# Mach_dieu_khien_tu_xa.net
KiCad netlist of a schematic drawn in Altium Designer
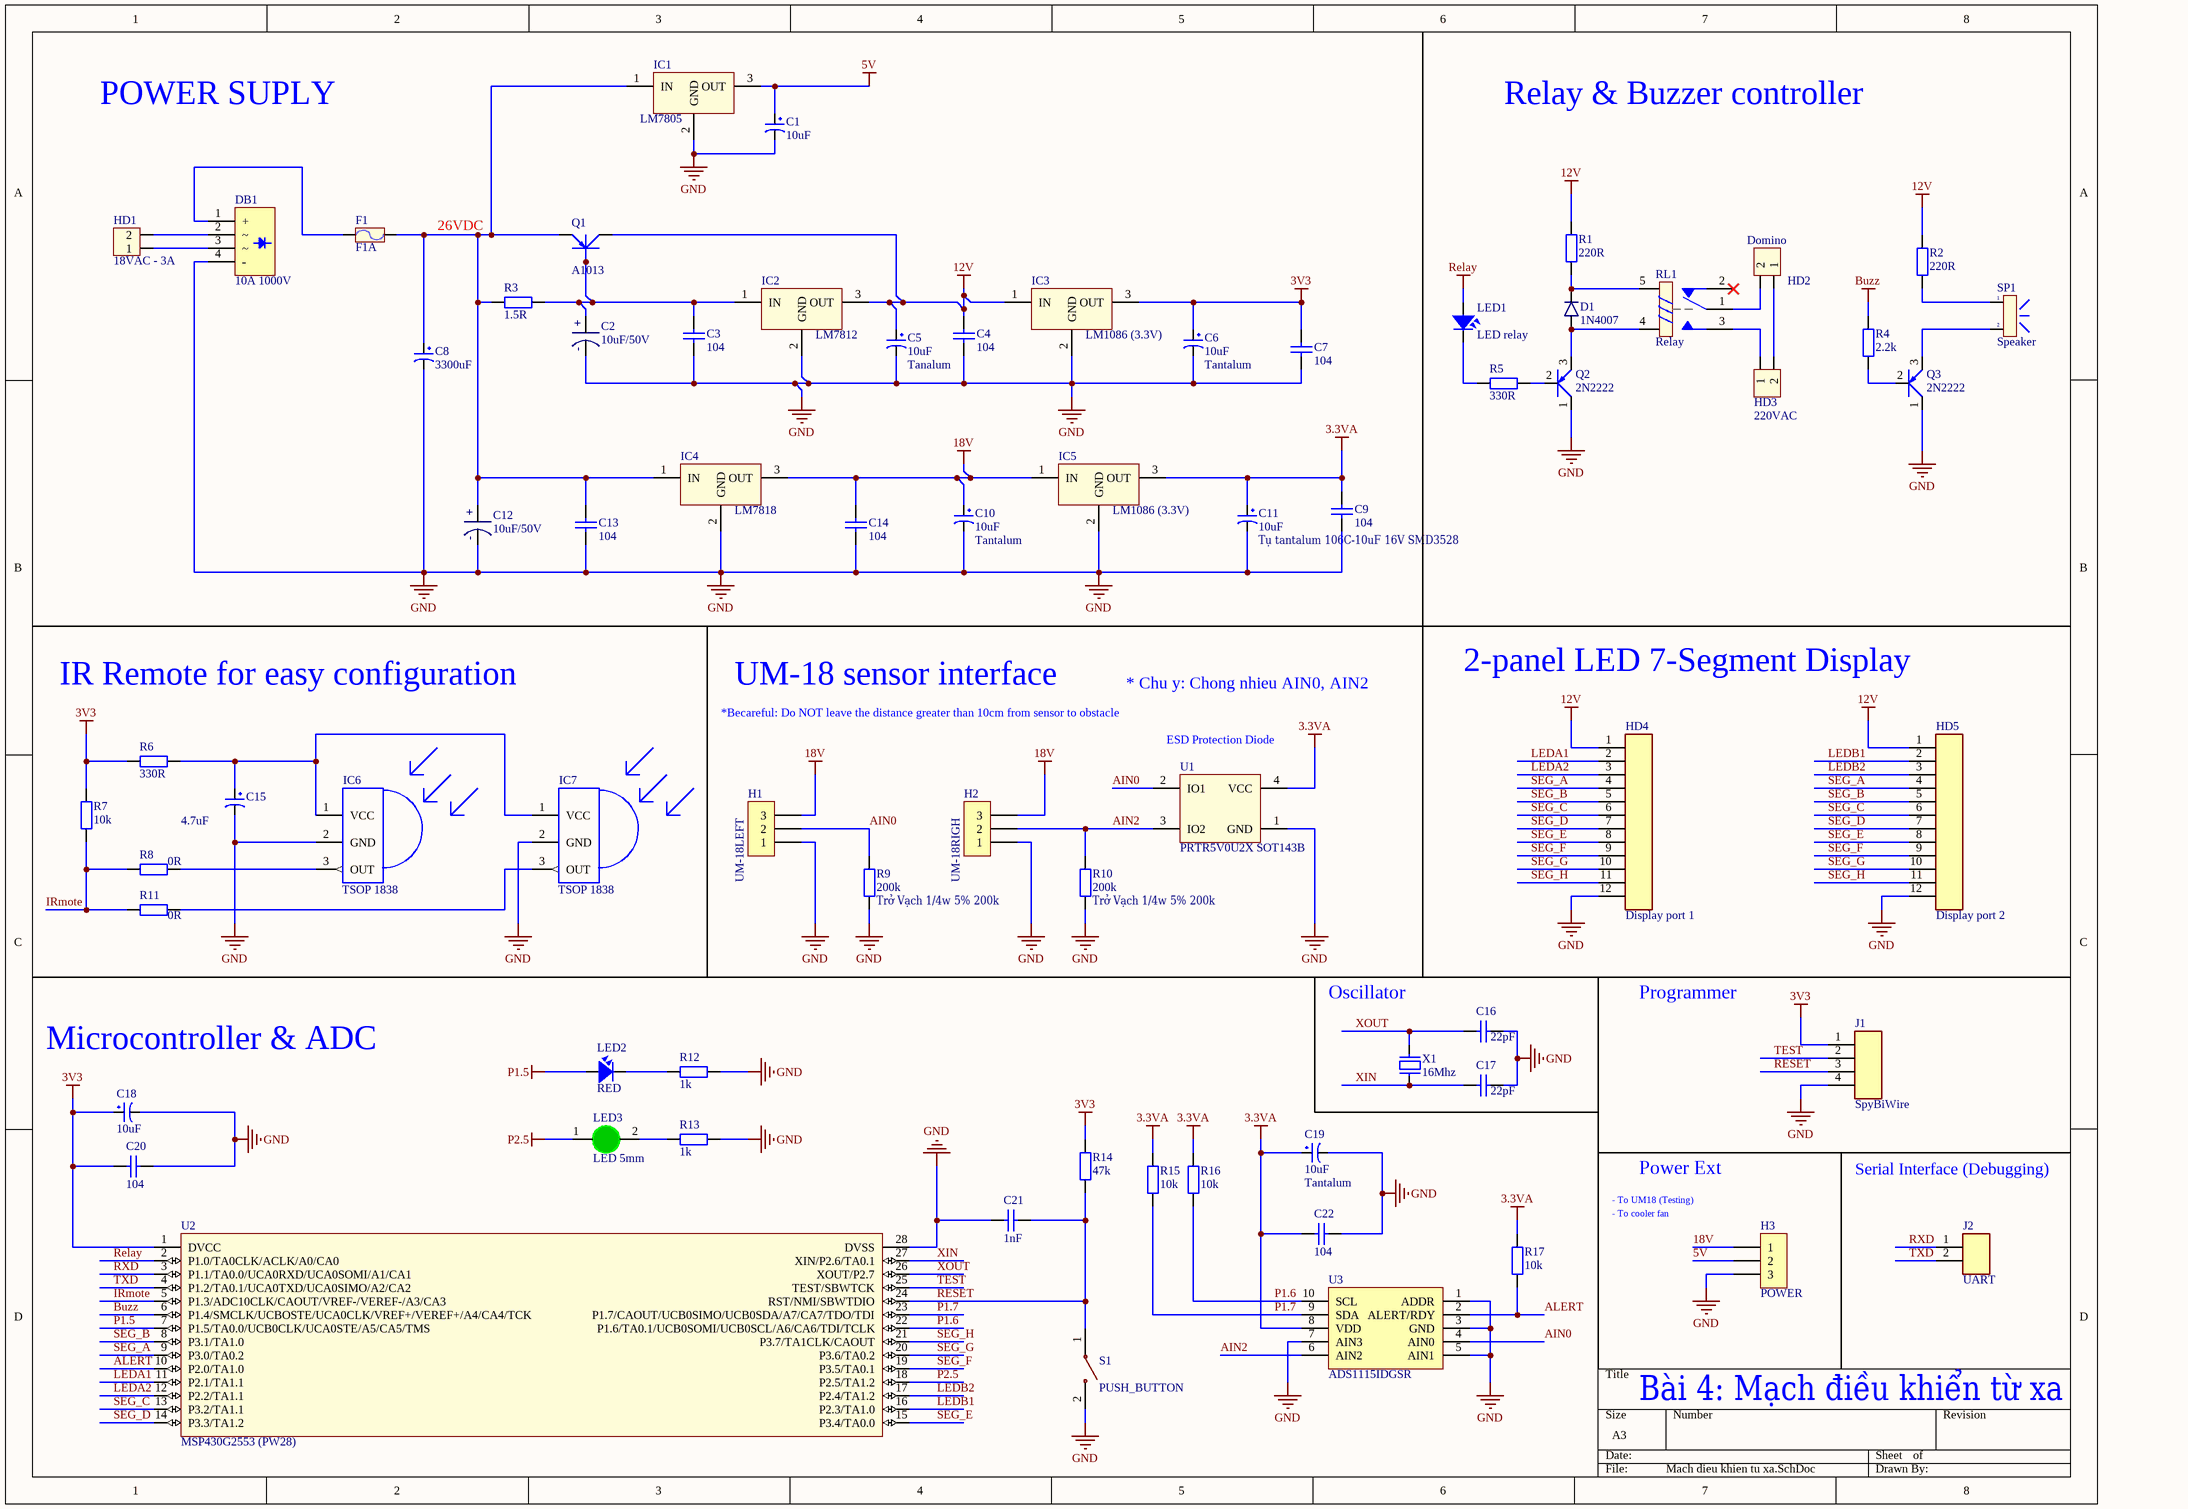
[diagram p0: Mach dieu khien tu xa.SchDoc]

(export (version "E")
  (design (tool "Eeschema 10.0.6"))
  (components
    (comp (ref "C1")
      (value "10uF")
      (footprint "tu hoa 4mm")
      (description "Cắm")
      (libsource (lib "") (part "Tu Hoa 10uF 16V 4x7_1"))
    )
    (comp (ref "C2")
      (value "10uF/50V")
      (footprint "10uF/50V")
      (description "Electrolytic Capacitor 10uF/50V")
      (libsource (lib "Tu dien") (part "10uF/50V"))
    )
    (comp (ref "C3")
      (value "104")
      (footprint "tu gom")
      (description "Cắm")
      (libsource (lib "Tu dien") (part "Tu gom 104 50V"))
    )
    (comp (ref "C4")
      (value "104")
      (footprint "tu gom")
      (description "Cắm")
      (libsource (lib "Tu dien") (part "Tu gom 104 50V"))
    )
    (comp (ref "C5")
      (value "10uF")
      (footprint "tu tantalum smd6032")
      (description "Dán")
      (fields (field (name "TEN_LINH_KIEN") "Tanalum"))
      (libsource (lib "Tu dien") (part "Tu tantalum 10uF 35V SMD6032"))
    )
    (comp (ref "C6")
      (value "10uF")
      (footprint "tu tantalum smd3528")
      (description "Dán")
      (fields (field (name "TEN_LINH_KIEN") "Tantalum"))
      (libsource (lib "Tu dien") (part "Tu tantalum 10uF 16V SMD3528"))
    )
    (comp (ref "C7")
      (value "104")
      (footprint "tu gom")
      (description "Cắm")
      (libsource (lib "Tu dien") (part "Tu gom 104 50V"))
    )
    (comp (ref "C8")
      (value "3300uF")
      (footprint "tu hoa 18mm")
      (description "Cắm")
      (libsource (lib "Tu dien") (part "Tu Hoa 3300uF 50V 18x35"))
    )
    (comp (ref "C9")
      (value "104")
      (footprint "tu gom")
      (description "Cắm")
      (libsource (lib "Tu dien") (part "Tu gom 104 50V"))
    )
    (comp (ref "C10")
      (value "10uF")
      (footprint "tu tantalum smd6032")
      (description "Dán")
      (fields (field (name "TEN_LINH_KIEN") "Tantalum"))
      (libsource (lib "Tu dien") (part "Tu tantalum 10uF 35V SMD6032"))
    )
    (comp (ref "C11")
      (value "10uF")
      (footprint "tu tantalum smd3528")
      (description "Dán")
      (fields (field (name "TEN_LINH_KIEN") "Tụ tantalum 106C-10uF 16V SMD3528"))
      (libsource (lib "Tu dien") (part "Tu tantalum 10uF 16V SMD3528"))
    )
    (comp (ref "C12")
      (value "10uF/50V")
      (footprint "10uF/50V")
      (description "Electrolytic Capacitor 10uF/50V")
      (libsource (lib "Tu dien") (part "10uF/50V"))
    )
    (comp (ref "C13")
      (value "104")
      (footprint "tu gom")
      (description "Cắm")
      (libsource (lib "Tu dien") (part "Tu gom 104 50V"))
    )
    (comp (ref "C14")
      (value "104")
      (footprint "tu gom")
      (description "Cắm")
      (libsource (lib "Tu dien") (part "Tu gom 104 50V"))
    )
    (comp (ref "C15")
      (value "4.7uF")
      (footprint "tu tantalum smd3216")
      (description "Dán")
      (libsource (lib "Tu dien") (part "Tu tantalum 4.7uF 16V SMD3216"))
    )
    (comp (ref "C16")
      (value "22pF")
      (footprint "tu gom")
      (description "Cắm")
      (libsource (lib "Tu dien") (part "Tu gom 22pF 50V"))
    )
    (comp (ref "C17")
      (value "22pF")
      (footprint "tu gom")
      (description "Cắm")
      (libsource (lib "Tu dien") (part "Tu gom 22pF 50V"))
    )
    (comp (ref "C18")
      (value "10uF")
      (footprint "tu hoa 4mm")
      (description "Cắm")
      (libsource (lib "Tu dien") (part "Tu Hoa 10uF 16V 4x7"))
    )
    (comp (ref "C19")
      (value "10uF")
      (footprint "tu tantalum smd3216")
      (description "Dán")
      (fields (field (name "TEN_LINH_KIEN") "Tantalum"))
      (libsource (lib "Tu dien") (part "Tu tantalum 10uF 16V SMD3216"))
    )
    (comp (ref "C20")
      (value "104")
      (footprint "tu gom")
      (description "Cắm")
      (libsource (lib "Tu dien") (part "Tu gom 104 50V"))
    )
    (comp (ref "C21")
      (value "1nF")
      (footprint "tu tantalum dip5.08")
      (description "Cắm")
      (libsource (lib "Tu dien") (part "Tu tantalum 1nF 50V 20% DIP5.08"))
    )
    (comp (ref "C22")
      (value "104")
      (footprint "tu gom")
      (description "Cắm")
      (libsource (lib "Tu dien") (part "Tu gom 104 50V"))
    )
    (comp (ref "D1")
      (value "1N4007")
      (footprint "1N4007")
      (description "Rectifier Diode 1000V 1A DO-41")
      (libsource (lib "Diode") (part "1N4007"))
    )
    (comp (ref "DB1")
      (value "10A 1000V")
      (footprint "DIODE CAU 10A CAM")
      (description "Cắm")
      (libsource (lib "Diode") (part "Diode CAU 10A"))
    )
    (comp (ref "F1")
      (value "F1A")
      (footprint "Fuse")
      (description "Fuse")
      (fields (field (name "DESIGNED BY") "VanDungEvn"))
      (libsource (lib "syhaunguyen") (part "Fuse"))
    )
    (comp (ref "H1")
      (value "UM-18LEFT")
      (footprint "XH2.54M-3")
      (description "Cắm")
      (libsource (lib "Header") (part "Header 3P 2.54 Duc Thang"))
    )
    (comp (ref "H2")
      (value "UM-18RIGH")
      (footprint "XH2.54M-3")
      (description "Cắm")
      (libsource (lib "Header") (part "Header 3P 2.54 Duc Thang"))
    )
    (comp (ref "H3")
      (value "POWER")
      (footprint "XH2.54M-3")
      (description "Cắm")
      (libsource (lib "") (part "Header 3P 2.54 Duc Thang_1"))
    )
    (comp (ref "HD1")
      (value "18VAC - 3A")
      (footprint "HED2")
      (description "Header 2 (Green)")
      (libsource (lib "syhaunguyen") (part "Hed2"))
    )
    (comp (ref "HD2")
      (value "Domino")
      (footprint "HED2")
      (description "Header 2 (Green)")
      (libsource (lib "") (part "Hed2_1"))
    )
    (comp (ref "HD3")
      (value "220VAC")
      (footprint "HED2")
      (description "Header 2 (Green)")
      (libsource (lib "syhaunguyen") (part "Hed2"))
    )
    (comp (ref "HD4")
      (value "Display port 1")
      (footprint "JST-2.5-12P")
      (libsource (lib "Connector") (part "JST-2.5-12P"))
    )
    (comp (ref "HD5")
      (value "Display port 2")
      (footprint "JST-2.5-12P")
      (libsource (lib "Connector") (part "JST-2.5-12P"))
    )
    (comp (ref "IC1")
      (value "LM7805")
      (footprint "QTO-220")
      (description "On ap +, from + 5 to + 24VDC")
      (libsource (lib "syhaunguyen") (part "LM78xx"))
    )
    (comp (ref "IC2")
      (value "LM7812")
      (footprint "QTO-220")
      (description "On ap +, from + 5 to + 24VDC")
      (libsource (lib "syhaunguyen") (part "LM78xx"))
    )
    (comp (ref "IC3")
      (value "LM1086 (3.3V)")
      (footprint "QTO-220")
      (description "On ap +, from + 5 to + 24VDC")
      (libsource (lib "syhaunguyen") (part "LM78xx"))
    )
    (comp (ref "IC4")
      (value "LM7818")
      (footprint "QTO-220")
      (description "On ap +, from + 5 to + 24VDC")
      (libsource (lib "syhaunguyen") (part "LM78xx"))
    )
    (comp (ref "IC5")
      (value "LM1086 (3.3V)")
      (footprint "QTO-220")
      (description "On ap +, from + 5 to + 24VDC")
      (libsource (lib "syhaunguyen") (part "LM78xx"))
    )
    (comp (ref "IC6")
      (value "TSOP 1838")
      (footprint "TSOP1838")
      (libsource (lib "Component") (part "TSOP 1838"))
    )
    (comp (ref "IC7")
      (value "TSOP 1838")
      (footprint "TSOP1838")
      (libsource (lib "Component") (part "TSOP 1838"))
    )
    (comp (ref "J1")
      (value "SpyBiWire")
      (footprint "MALE-2.54-4P")
      (description "Male Header Connector 2.54mm 4 Pins.")
      (libsource (lib "Connector") (part "MALE-2.54-4P"))
    )
    (comp (ref "J2")
      (value "UART")
      (footprint "MALE-2.54-2P")
      (description "Male Header Connector 2.54mm 2 Pins.")
      (libsource (lib "Connector") (part "MALE-2.54-2P"))
    )
    (comp (ref "LED1")
      (value "LED relay")
      (footprint "LED-5-RED")
      (description "LED Single colour Green and Red")
      (libsource (lib "syhaunguyen") (part "LED"))
    )
    (comp (ref "LED2")
      (value "RED")
      (footprint "LED-5-RED")
      (description "LED Single colour Green and Red")
      (libsource (lib "syhaunguyen") (part "LED"))
    )
    (comp (ref "LED3")
      (value "LED 5mm")
      (footprint "LED-5MM-Green")
      (description "Cắm")
      (libsource (lib "Led") (part "LED 5mm Xanh La"))
    )
    (comp (ref "Q1")
      (value "A1013")
      (footprint "QTO-92")
      (description "P 600mW, ECB")
      (libsource (lib "syhaunguyen") (part "PNP_ECB"))
    )
    (comp (ref "Q2")
      (value "2N2222")
      (footprint "2N2222")
      (description "NPN switching transistor in a TO-18 metal package.")
      (libsource (lib "TranFet") (part "2N2222"))
    )
    (comp (ref "Q3")
      (value "2N2222")
      (footprint "2N2222")
      (description "NPN switching transistor in a TO-18 metal package.")
      (libsource (lib "TranFet") (part "2N2222"))
    )
    (comp (ref "R1")
      (value "220R")
      (footprint "tro vach 1w")
      (description "Cắm")
      (libsource (lib "Dien Tro") (part "Tro Vach 1W 5% 220R"))
    )
    (comp (ref "R2")
      (value "220R")
      (footprint "tro vach 1w")
      (description "Cắm")
      (libsource (lib "Dien Tro") (part "Tro Vach 1W 5% 220R"))
    )
    (comp (ref "R3")
      (value "1.5R")
      (footprint "tro vach 2w")
      (description "Cắm")
      (libsource (lib "Dien Tro") (part "Tro Vach 2W 1% 1.5R"))
    )
    (comp (ref "R4")
      (value "2.2k")
      (footprint "tro vach 1/4w")
      (description "Cắm")
      (libsource (lib "Dien Tro") (part "Tro Vach 1/4W 5% 2.2k"))
    )
    (comp (ref "R5")
      (value "330R")
      (footprint "tro vach 1/4w")
      (description "Cắm")
      (libsource (lib "Dien Tro") (part "Tro Vach 1/4W 1% 330R"))
    )
    (comp (ref "R6")
      (value "330R")
      (footprint "tro vach 2w")
      (description "Cắm")
      (libsource (lib "Dien Tro") (part "Tro Vach 2W 5% 330R"))
    )
    (comp (ref "R7")
      (value "10k")
      (footprint "tro vach 2w")
      (description "Cắm")
      (libsource (lib "Dien Tro") (part "Tro Vach 2W 5% 10k"))
    )
    (comp (ref "R8")
      (value "0R")
      (footprint "tro smd 0603")
      (description "Dán")
      (libsource (lib "Dien Tro") (part "Tro 0603 1% 0R"))
    )
    (comp (ref "R9")
      (value "200k")
      (footprint "tro vach 1/4w")
      (description "Cắm")
      (fields (field (name "TEN_LINH_KIEN") "Trở Vạch 1/4w 5% 200k"))
      (libsource (lib "Dien Tro") (part "Tro Vach 1/4W 5% 200k"))
    )
    (comp (ref "R10")
      (value "200k")
      (footprint "tro vach 1/4w")
      (description "Cắm")
      (fields (field (name "TEN_LINH_KIEN") "Trở Vạch 1/4w 5% 200k"))
      (libsource (lib "Dien Tro") (part "Tro Vach 1/4W 5% 200k"))
    )
    (comp (ref "R11")
      (value "0R")
      (footprint "tro smd 0603")
      (description "Dán")
      (libsource (lib "Dien Tro") (part "Tro 0603 1% 0R"))
    )
    (comp (ref "R12")
      (value "1k")
      (footprint "tro vach 1w")
      (description "Cắm")
      (libsource (lib "Dien Tro") (part "Tro Vach 1W 5% 1k"))
    )
    (comp (ref "R13")
      (value "1k")
      (footprint "tro vach 1w")
      (description "Cắm")
      (libsource (lib "Dien Tro") (part "Tro Vach 1W 5% 1k"))
    )
    (comp (ref "R14")
      (value "47k")
      (footprint "tro vach 1/4w")
      (description "Cắm")
      (libsource (lib "Dien Tro") (part "Tro Vach 1/4W 5% 47k"))
    )
    (comp (ref "R15")
      (value "10k")
      (footprint "tro vach 1/4w")
      (description "Căm")
      (libsource (lib "Dien Tro") (part "Tro Vach 1/4W 5% 10k"))
    )
    (comp (ref "R16")
      (value "10k")
      (footprint "tro vach 1/4w")
      (description "Căm")
      (libsource (lib "Dien Tro") (part "Tro Vach 1/4W 5% 10k"))
    )
    (comp (ref "R17")
      (value "10k")
      (footprint "tro vach 1/4w")
      (description "Căm")
      (libsource (lib "Dien Tro") (part "Tro Vach 1/4W 5% 10k"))
    )
    (comp (ref "RL1")
      (value "Relay")
      (footprint "Relay 5 Chan SRD")
      (description "Relay 5 Chan")
      (libsource (lib "Component") (part "Relay 5 Chan SRD"))
    )
    (comp (ref "S1")
      (value "PUSH_BUTTON")
      (footprint "PUSH_BUTTON_SMD_3X4X2")
      (description "Push Button Tactile Switch SMD 2 Pins 3x4x2mm.")
      (libsource (lib "Buttons & Switches") (part "PUSH_BUTTON_SMD_3X4X2"))
    )
    (comp (ref "SP1")
      (value "Speaker")
      (footprint "SPK")
      (description "Speaker Chip")
      (libsource (lib "syhaunguyen") (part "SPK"))
    )
    (comp (ref "U1")
      (value "PRTR5V0U2X SOT143B")
      (footprint "PRTR5V0U2X")
      (libsource (lib "IC") (part "PRTR5V0U2X"))
    )
    (comp (ref "U2")
      (value "MSP430G2553 (PW28)")
      (footprint "MSP430G2553 (PW28)")
      (libsource (lib "TV NQM") (part "MSP430G2553 (PW28)"))
    )
    (comp (ref "U3")
      (value "ADS1115IDGSR")
      (footprint "VSOP-10_19.6_230_57X12_SMD")
      (description "Analog to Digital Converters - ADC 16B ADC w/ Int MUX PGA Comp Osc & Ref")
      (fields (field (name "MANUFACTURER") "Texas Instruments"))
      (libsource (lib "IC") (part "IC_ADS1115IDGSR"))
    )
    (comp (ref "X1")
      (value "16Mhz")
      (footprint "Thach Anh 2 chan cam")
      (description "Crystal For all Crystal 2pin.")
      (libsource (lib "Component") (part "Thach Anh 2 chan Cam"))
    )
  )
  (nets
    (net (code "1") (name "/AIN0") (class "Default")
      (node (ref "H1") (pin "2") (pinfunction "2_2") (pintype "passive"))
      (node (ref "R9") (pin "2") (pinfunction "2_2") (pintype "passive"))
      (node (ref "U1") (pin "2") (pinfunction "IO1_2") (pintype "passive"))
      (node (ref "U3") (pin "4") (pinfunction "AIN0_4") (pintype "passive"))
    )
    (net (code "2") (name "/AIN2") (class "Default")
      (node (ref "H2") (pin "2") (pinfunction "2_2") (pintype "passive"))
      (node (ref "R10") (pin "2") (pinfunction "2_2") (pintype "passive"))
      (node (ref "U1") (pin "3") (pinfunction "IO2_3") (pintype "passive"))
      (node (ref "U3") (pin "6") (pinfunction "AIN2_6") (pintype "passive"))
    )
    (net (code "3") (name "/ALERT") (class "Default")
      (node (ref "R17") (pin "1") (pinfunction "1_1") (pintype "passive"))
      (node (ref "U2") (pin "10") (pinfunction "P2.0/TA1.0_10") (pintype "bidirectional"))
      (node (ref "U3") (pin "2") (pinfunction "ALERT/RDY_2") (pintype "passive"))
    )
    (net (code "4") (name "/IRmote") (class "Default")
      (node (ref "R11") (pin "1") (pinfunction "1_1") (pintype "passive"))
      (node (ref "R7") (pin "1") (pinfunction "1_1") (pintype "passive"))
      (node (ref "R8") (pin "1") (pinfunction "1_1") (pintype "passive"))
      (node (ref "U2") (pin "5") (pinfunction "P1.3/ADC10CLK/CAOUT/VREF-/VEREF-/A3/CA3_5") (pintype "bidirectional"))
    )
    (net (code "5") (name "/LEDA1") (class "Default")
      (node (ref "HD4") (pin "2") (pintype "passive"))
      (node (ref "U2") (pin "11") (pinfunction "P2.1/TA1.1_11") (pintype "bidirectional"))
    )
    (net (code "6") (name "/LEDA2") (class "Default")
      (node (ref "HD4") (pin "3") (pintype "passive"))
      (node (ref "U2") (pin "12") (pinfunction "P2.2/TA1.1_12") (pintype "bidirectional"))
    )
    (net (code "7") (name "/LEDB1") (class "Default")
      (node (ref "HD5") (pin "2") (pintype "passive"))
      (node (ref "U2") (pin "16") (pinfunction "P2.3/TA1.0_16") (pintype "bidirectional"))
    )
    (net (code "8") (name "/LEDB2") (class "Default")
      (node (ref "HD5") (pin "3") (pintype "passive"))
      (node (ref "U2") (pin "17") (pinfunction "P2.4/TA1.2_17") (pintype "bidirectional"))
    )
    (net (code "9") (name "/P1.6") (class "Default")
      (node (ref "R16") (pin "1") (pinfunction "1_1") (pintype "passive"))
      (node (ref "U2") (pin "22") (pinfunction "P1.6/TA0.1/UCB0SOMI/UCB0SCL/A6/CA6/TDI/TCLK_22") (pintype "bidirectional"))
      (node (ref "U3") (pin "10") (pinfunction "SCL_10") (pintype "passive"))
    )
    (net (code "10") (name "/P1.7") (class "Default")
      (node (ref "R15") (pin "1") (pinfunction "1_1") (pintype "passive"))
      (node (ref "U2") (pin "23") (pinfunction "P1.7/CAOUT/UCB0SIMO/UCB0SDA/A7/CA7/TDO/TDI_23") (pintype "bidirectional"))
      (node (ref "U3") (pin "9") (pinfunction "SDA_9") (pintype "passive"))
    )
    (net (code "11") (name "/RESET") (class "Default")
      (node (ref "C21") (pin "1") (pinfunction "1_1") (pintype "passive"))
      (node (ref "J1") (pin "3") (pintype "passive"))
      (node (ref "R14") (pin "1") (pinfunction "1_1") (pintype "passive"))
      (node (ref "S1") (pin "1") (pinfunction "1_1") (pintype "passive"))
      (node (ref "U2") (pin "24") (pinfunction "RST/NMI/SBWTDIO_24") (pintype "bidirectional"))
    )
    (net (code "12") (name "/RXD") (class "Default")
      (node (ref "J2") (pin "1") (pintype "passive"))
      (node (ref "U2") (pin "3") (pinfunction "P1.1/TA0.0/UCA0RXD/UCA0SOMI/A1/CA1_3") (pintype "bidirectional"))
    )
    (net (code "13") (name "/SEG_A") (class "Default")
      (node (ref "HD4") (pin "4") (pintype "passive"))
      (node (ref "HD5") (pin "4") (pintype "passive"))
      (node (ref "U2") (pin "9") (pinfunction "P3.0/TA0.2_9") (pintype "bidirectional"))
    )
    (net (code "14") (name "/SEG_B") (class "Default")
      (node (ref "HD4") (pin "5") (pintype "passive"))
      (node (ref "HD5") (pin "5") (pintype "passive"))
      (node (ref "U2") (pin "8") (pinfunction "P3.1/TA1.0_8") (pintype "bidirectional"))
    )
    (net (code "15") (name "/SEG_C") (class "Default")
      (node (ref "HD4") (pin "6") (pintype "passive"))
      (node (ref "HD5") (pin "6") (pintype "passive"))
      (node (ref "U2") (pin "13") (pinfunction "P3.2/TA1.1_13") (pintype "bidirectional"))
    )
    (net (code "16") (name "/SEG_D") (class "Default")
      (node (ref "HD4") (pin "7") (pintype "passive"))
      (node (ref "HD5") (pin "7") (pintype "passive"))
      (node (ref "U2") (pin "14") (pinfunction "P3.3/TA1.2_14") (pintype "bidirectional"))
    )
    (net (code "17") (name "/SEG_E") (class "Default")
      (node (ref "HD4") (pin "8") (pintype "passive"))
      (node (ref "HD5") (pin "8") (pintype "passive"))
      (node (ref "U2") (pin "15") (pinfunction "P3.4/TA0.0_15") (pintype "bidirectional"))
    )
    (net (code "18") (name "/SEG_F") (class "Default")
      (node (ref "HD4") (pin "9") (pintype "passive"))
      (node (ref "HD5") (pin "9") (pintype "passive"))
      (node (ref "U2") (pin "19") (pinfunction "P3.5/TA0.1_19") (pintype "bidirectional"))
    )
    (net (code "19") (name "/SEG_G") (class "Default")
      (node (ref "HD4") (pin "10") (pintype "passive"))
      (node (ref "HD5") (pin "10") (pintype "passive"))
      (node (ref "U2") (pin "20") (pinfunction "P3.6/TA0.2_20") (pintype "bidirectional"))
    )
    (net (code "20") (name "/SEG_H") (class "Default")
      (node (ref "HD4") (pin "11") (pintype "passive"))
      (node (ref "HD5") (pin "11") (pintype "passive"))
      (node (ref "U2") (pin "21") (pinfunction "P3.7/TA1CLK/CAOUT_21") (pintype "bidirectional"))
    )
    (net (code "21") (name "/TEST") (class "Default")
      (node (ref "J1") (pin "2") (pintype "passive"))
      (node (ref "U2") (pin "25") (pinfunction "TEST/SBWTCK_25") (pintype "bidirectional"))
    )
    (net (code "22") (name "/TXD") (class "Default")
      (node (ref "J2") (pin "2") (pintype "passive"))
      (node (ref "U2") (pin "4") (pinfunction "P1.2/TA0.1/UCA0TXD/UCA0SIMO/A2/CA2_4") (pintype "bidirectional"))
    )
    (net (code "23") (name "/XIN") (class "Default")
      (node (ref "C17") (pin "2") (pinfunction "2_2") (pintype "passive"))
      (node (ref "U2") (pin "27") (pinfunction "XIN/P2.6/TA0.1_27") (pintype "bidirectional"))
      (node (ref "X1") (pin "1") (pinfunction "1_1") (pintype "passive"))
    )
    (net (code "24") (name "/XOUT") (class "Default")
      (node (ref "C16") (pin "2") (pinfunction "2_2") (pintype "passive"))
      (node (ref "U2") (pin "26") (pinfunction "XOUT/P2.7_26") (pintype "bidirectional"))
      (node (ref "X1") (pin "2") (pinfunction "2_2") (pintype "passive"))
    )
    (net (code "25") (name "3.3VA") (class "Default")
      (node (ref "C11") (pin "1") (pinfunction "1_1") (pintype "passive"))
      (node (ref "C19") (pin "1") (pinfunction "1_1") (pintype "passive"))
      (node (ref "C22") (pin "1") (pinfunction "1_1") (pintype "passive"))
      (node (ref "C9") (pin "1") (pinfunction "1_1") (pintype "passive"))
      (node (ref "IC5") (pin "3") (pinfunction "OUT_3") (pintype "passive"))
      (node (ref "R15") (pin "2") (pinfunction "2_2") (pintype "passive"))
      (node (ref "R16") (pin "2") (pinfunction "2_2") (pintype "passive"))
      (node (ref "R17") (pin "2") (pinfunction "2_2") (pintype "passive"))
      (node (ref "U1") (pin "4") (pinfunction "VCC_4") (pintype "passive"))
      (node (ref "U3") (pin "8") (pinfunction "VDD_8") (pintype "passive"))
    )
    (net (code "26") (name "3V3") (class "Default")
      (node (ref "C18") (pin "1") (pinfunction "1_1") (pintype "passive"))
      (node (ref "C20") (pin "1") (pinfunction "1_1") (pintype "passive"))
      (node (ref "C6") (pin "1") (pinfunction "1_1") (pintype "passive"))
      (node (ref "C7") (pin "1") (pinfunction "1_1") (pintype "passive"))
      (node (ref "IC3") (pin "3") (pinfunction "OUT_3") (pintype "passive"))
      (node (ref "J1") (pin "1") (pintype "passive"))
      (node (ref "R14") (pin "2") (pinfunction "2_2") (pintype "passive"))
      (node (ref "R6") (pin "1") (pinfunction "1_1") (pintype "passive"))
      (node (ref "R7") (pin "2") (pinfunction "2_2") (pintype "passive"))
      (node (ref "U2") (pin "1") (pinfunction "DVCC_1") (pintype "passive"))
    )
    (net (code "27") (name "5V") (class "Default")
      (node (ref "C1") (pin "1") (pinfunction "1_1") (pintype "passive"))
      (node (ref "H3") (pin "2") (pinfunction "2_2") (pintype "passive"))
      (node (ref "IC1") (pin "3") (pinfunction "OUT_3") (pintype "passive"))
    )
    (net (code "28") (name "12V") (class "Default")
      (node (ref "C4") (pin "1") (pinfunction "1_1") (pintype "passive"))
      (node (ref "C5") (pin "1") (pinfunction "1_1") (pintype "passive"))
      (node (ref "HD4") (pin "1") (pintype "passive"))
      (node (ref "HD5") (pin "1") (pintype "passive"))
      (node (ref "IC2") (pin "3") (pinfunction "OUT_3") (pintype "passive"))
      (node (ref "IC3") (pin "1") (pinfunction "IN_1") (pintype "passive"))
      (node (ref "Q1") (pin "2") (pinfunction "C_2") (pintype "passive"))
      (node (ref "R1") (pin "2") (pinfunction "2_2") (pintype "passive"))
      (node (ref "R2") (pin "2") (pinfunction "2_2") (pintype "passive"))
    )
    (net (code "29") (name "18V") (class "Default")
      (node (ref "C10") (pin "1") (pinfunction "1_1") (pintype "passive"))
      (node (ref "C14") (pin "1") (pinfunction "1_1") (pintype "passive"))
      (node (ref "H1") (pin "3") (pinfunction "3_3") (pintype "passive"))
      (node (ref "H2") (pin "3") (pinfunction "3_3") (pintype "passive"))
      (node (ref "H3") (pin "1") (pinfunction "1_1") (pintype "passive"))
      (node (ref "IC4") (pin "3") (pinfunction "OUT_3") (pintype "passive"))
      (node (ref "IC5") (pin "1") (pinfunction "IN_1") (pintype "passive"))
    )
    (net (code "30") (name "Buzz") (class "Default")
      (node (ref "R4") (pin "2") (pinfunction "2_2") (pintype "passive"))
      (node (ref "U2") (pin "6") (pinfunction "P1.4/SMCLK/UCBOSTE/UCA0CLK/VREF+/VEREF+/A4/CA4/TCK_6") (pintype "bidirectional"))
    )
    (net (code "31") (name "GND") (class "Default")
      (node (ref "C1") (pin "2") (pinfunction "2_2") (pintype "passive"))
      (node (ref "C10") (pin "2") (pinfunction "2_2") (pintype "passive"))
      (node (ref "C11") (pin "2") (pinfunction "2_2") (pintype "passive"))
      (node (ref "C12") (pin "1") (pinfunction "1_1") (pintype "passive"))
      (node (ref "C13") (pin "2") (pinfunction "2_2") (pintype "passive"))
      (node (ref "C14") (pin "2") (pinfunction "2_2") (pintype "passive"))
      (node (ref "C15") (pin "2") (pinfunction "2_2") (pintype "passive"))
      (node (ref "C16") (pin "1") (pinfunction "1_1") (pintype "passive"))
      (node (ref "C17") (pin "1") (pinfunction "1_1") (pintype "passive"))
      (node (ref "C18") (pin "2") (pinfunction "2_2") (pintype "passive"))
      (node (ref "C19") (pin "2") (pinfunction "2_2") (pintype "passive"))
      (node (ref "C2") (pin "1") (pinfunction "1_1") (pintype "passive"))
      (node (ref "C20") (pin "2") (pinfunction "2_2") (pintype "passive"))
      (node (ref "C21") (pin "2") (pinfunction "2_2") (pintype "passive"))
      (node (ref "C22") (pin "2") (pinfunction "2_2") (pintype "passive"))
      (node (ref "C3") (pin "2") (pinfunction "2_2") (pintype "passive"))
      (node (ref "C4") (pin "2") (pinfunction "2_2") (pintype "passive"))
      (node (ref "C5") (pin "2") (pinfunction "2_2") (pintype "passive"))
      (node (ref "C6") (pin "2") (pinfunction "2_2") (pintype "passive"))
      (node (ref "C7") (pin "2") (pinfunction "2_2") (pintype "passive"))
      (node (ref "C8") (pin "2") (pinfunction "2_2") (pintype "passive"))
      (node (ref "C9") (pin "2") (pinfunction "2_2") (pintype "passive"))
      (node (ref "DB1") (pin "4") (pinfunction "-_4") (pintype "passive"))
      (node (ref "H1") (pin "1") (pinfunction "1_1") (pintype "passive"))
      (node (ref "H2") (pin "1") (pinfunction "1_1") (pintype "passive"))
      (node (ref "H3") (pin "3") (pinfunction "3_3") (pintype "passive"))
      (node (ref "HD4") (pin "12") (pintype "passive"))
      (node (ref "HD5") (pin "12") (pintype "passive"))
      (node (ref "IC1") (pin "2") (pinfunction "GND_2") (pintype "passive"))
      (node (ref "IC2") (pin "2") (pinfunction "GND_2") (pintype "passive"))
      (node (ref "IC3") (pin "2") (pinfunction "GND_2") (pintype "passive"))
      (node (ref "IC4") (pin "2") (pinfunction "GND_2") (pintype "passive"))
      (node (ref "IC5") (pin "2") (pinfunction "GND_2") (pintype "passive"))
      (node (ref "IC6") (pin "2") (pinfunction "GND_2") (pintype "passive"))
      (node (ref "IC7") (pin "2") (pinfunction "GND_2") (pintype "passive"))
      (node (ref "J1") (pin "4") (pintype "passive"))
      (node (ref "Q2") (pin "1") (pinfunction "E_1") (pintype "passive"))
      (node (ref "Q3") (pin "1") (pinfunction "E_1") (pintype "passive"))
      (node (ref "R10") (pin "1") (pinfunction "1_1") (pintype "passive"))
      (node (ref "R12") (pin "2") (pinfunction "2_2") (pintype "passive"))
      (node (ref "R13") (pin "2") (pinfunction "2_2") (pintype "passive"))
      (node (ref "R9") (pin "1") (pinfunction "1_1") (pintype "passive"))
      (node (ref "S1") (pin "2") (pinfunction "2_2") (pintype "passive"))
      (node (ref "U1") (pin "1") (pinfunction "GND_1") (pintype "passive"))
      (node (ref "U2") (pin "28") (pinfunction "DVSS_28") (pintype "passive"))
      (node (ref "U3") (pin "1") (pinfunction "ADDR_1") (pintype "passive"))
      (node (ref "U3") (pin "3") (pinfunction "GND_3") (pintype "passive"))
      (node (ref "U3") (pin "5") (pinfunction "AIN1_5") (pintype "passive"))
      (node (ref "U3") (pin "7") (pinfunction "AIN3_7") (pintype "passive"))
    )
    (net (code "32") (name "Net-(C2-_2)") (class "Default")
      (node (ref "C2") (pin "2") (pinfunction "_2_2") (pintype "passive"))
      (node (ref "C3") (pin "1") (pinfunction "1_1") (pintype "passive"))
      (node (ref "IC2") (pin "1") (pinfunction "IN_1") (pintype "passive"))
      (node (ref "Q1") (pin "3") (pinfunction "B_3") (pintype "passive"))
      (node (ref "R3") (pin "2") (pinfunction "2_2") (pintype "passive"))
    )
    (net (code "33") (name "Net-(C12-_2)") (class "Default")
      (node (ref "C12") (pin "2") (pinfunction "_2_2") (pintype "passive"))
      (node (ref "C13") (pin "1") (pinfunction "1_1") (pintype "passive"))
      (node (ref "C8") (pin "1") (pinfunction "1_1") (pintype "passive"))
      (node (ref "F1") (pin "2") (pinfunction "2_2") (pintype "passive"))
      (node (ref "IC1") (pin "1") (pinfunction "IN_1") (pintype "passive"))
      (node (ref "IC4") (pin "1") (pinfunction "IN_1") (pintype "passive"))
      (node (ref "Q1") (pin "1") (pinfunction "E_1") (pintype "passive"))
      (node (ref "R3") (pin "1") (pinfunction "1_1") (pintype "passive"))
    )
    (net (code "34") (name "Net-(D1-Pad2)") (class "Default")
      (node (ref "D1") (pin "2") (pintype "passive"))
      (node (ref "R1") (pin "1") (pinfunction "1_1") (pintype "passive"))
      (node (ref "RL1") (pin "5") (pinfunction "5_5") (pintype "passive"))
    )
    (net (code "35") (name "Net-(DB1-+)") (class "Default")
      (node (ref "DB1") (pin "1") (pinfunction "+_1") (pintype "passive"))
      (node (ref "F1") (pin "1") (pinfunction "1_1") (pintype "passive"))
    )
    (net (code "36") (name "Net-(DB1-~-Pad2)") (class "Default")
      (node (ref "DB1") (pin "2") (pinfunction "~_2") (pintype "passive"))
      (node (ref "HD1") (pin "2") (pinfunction "2_2") (pintype "passive"))
    )
    (net (code "37") (name "Net-(DB1-~-Pad3)") (class "Default")
      (node (ref "DB1") (pin "3") (pinfunction "~_3") (pintype "passive"))
      (node (ref "HD1") (pin "1") (pinfunction "1_1") (pintype "passive"))
    )
    (net (code "38") (name "Net-(HD2-Pad1)") (class "Default")
      (node (ref "HD2") (pin "1") (pinfunction "1_1") (pintype "passive"))
      (node (ref "HD3") (pin "2") (pinfunction "2_2") (pintype "passive"))
    )
    (net (code "39") (name "Net-(HD2-Pad2)") (class "Default")
      (node (ref "HD2") (pin "2") (pinfunction "2_2") (pintype "passive"))
      (node (ref "RL1") (pin "1") (pinfunction "1_1") (pintype "passive"))
    )
    (net (code "40") (name "Net-(HD3-Pad1)") (class "Default")
      (node (ref "HD3") (pin "1") (pinfunction "1_1") (pintype "passive"))
      (node (ref "RL1") (pin "3") (pinfunction "3_3") (pintype "passive"))
    )
    (net (code "41") (name "Net-(IC6-OUT)") (class "Default")
      (node (ref "IC6") (pin "3") (pinfunction "OUT_3") (pintype "output"))
      (node (ref "R8") (pin "2") (pinfunction "2_2") (pintype "passive"))
    )
    (net (code "42") (name "Net-(IC6-VCC)") (class "Default")
      (node (ref "C15") (pin "1") (pinfunction "1_1") (pintype "passive"))
      (node (ref "IC6") (pin "1") (pinfunction "VCC_1") (pintype "passive"))
      (node (ref "IC7") (pin "1") (pinfunction "VCC_1") (pintype "passive"))
      (node (ref "R6") (pin "2") (pinfunction "2_2") (pintype "passive"))
    )
    (net (code "43") (name "Net-(IC7-OUT)") (class "Default")
      (node (ref "IC7") (pin "3") (pinfunction "OUT_3") (pintype "output"))
      (node (ref "R11") (pin "2") (pinfunction "2_2") (pintype "passive"))
    )
    (net (code "44") (name "Net-(LED1-Pad2)") (class "Default")
      (node (ref "LED1") (pin "2") (pinfunction "2_2") (pintype "passive"))
      (node (ref "R5") (pin "2") (pinfunction "2_2") (pintype "passive"))
    )
    (net (code "45") (name "Net-(LED2-Pad2)") (class "Default")
      (node (ref "LED2") (pin "2") (pinfunction "2_2") (pintype "passive"))
      (node (ref "R12") (pin "1") (pinfunction "1_1") (pintype "passive"))
    )
    (net (code "46") (name "Net-(LED3-K)") (class "Default")
      (node (ref "LED3") (pin "2") (pinfunction "K_2") (pintype "passive"))
      (node (ref "R13") (pin "1") (pinfunction "1_1") (pintype "passive"))
    )
    (net (code "47") (name "Net-(Q2-B)") (class "Default")
      (node (ref "Q2") (pin "2") (pinfunction "B_2") (pintype "passive"))
      (node (ref "R5") (pin "1") (pinfunction "1_1") (pintype "passive"))
    )
    (net (code "48") (name "Net-(Q2-C)") (class "Default")
      (node (ref "D1") (pin "1") (pinfunction "1_1") (pintype "passive"))
      (node (ref "Q2") (pin "3") (pinfunction "C_3") (pintype "passive"))
      (node (ref "RL1") (pin "4") (pinfunction "4_4") (pintype "passive"))
    )
    (net (code "49") (name "Net-(Q3-B)") (class "Default")
      (node (ref "Q3") (pin "2") (pinfunction "B_2") (pintype "passive"))
      (node (ref "R4") (pin "1") (pinfunction "1_1") (pintype "passive"))
    )
    (net (code "50") (name "Net-(Q3-C)") (class "Default")
      (node (ref "Q3") (pin "3") (pinfunction "C_3") (pintype "passive"))
      (node (ref "SP1") (pin "2") (pinfunction "2_2") (pintype "passive"))
    )
    (net (code "51") (name "Net-(R2-Pad1)") (class "Default")
      (node (ref "R2") (pin "1") (pinfunction "1_1") (pintype "passive"))
      (node (ref "SP1") (pin "1") (pinfunction "1_1") (pintype "passive"))
    )
    (net (code "52") (name "P1.5") (class "Default")
      (node (ref "LED2") (pin "1") (pinfunction "1_1") (pintype "passive"))
      (node (ref "U2") (pin "7") (pinfunction "P1.5/TA0.0/UCB0CLK/UCA0STE/A5/CA5/TMS_7") (pintype "bidirectional"))
    )
    (net (code "53") (name "P2.5") (class "Default")
      (node (ref "LED3") (pin "1") (pinfunction "A_1") (pintype "passive"))
      (node (ref "U2") (pin "18") (pinfunction "P2.5/TA1.2_18") (pintype "bidirectional"))
    )
    (net (code "54") (name "Relay") (class "Default")
      (node (ref "LED1") (pin "1") (pinfunction "1_1") (pintype "passive"))
      (node (ref "U2") (pin "2") (pinfunction "P1.0/TA0CLK/ACLK/A0/CA0_2") (pintype "bidirectional"))
    )
    (net (code "55") (name "unconnected-(RL1-Pad2)") (class "Default")
      (node (ref "RL1") (pin "2") (pinfunction "2_2") (pintype "passive+no_connect"))
    )
  )
)
